# LSWM_10_STM32L0_ADXL345.net
KiCad netlist of a schematic drawn in Altium Designer
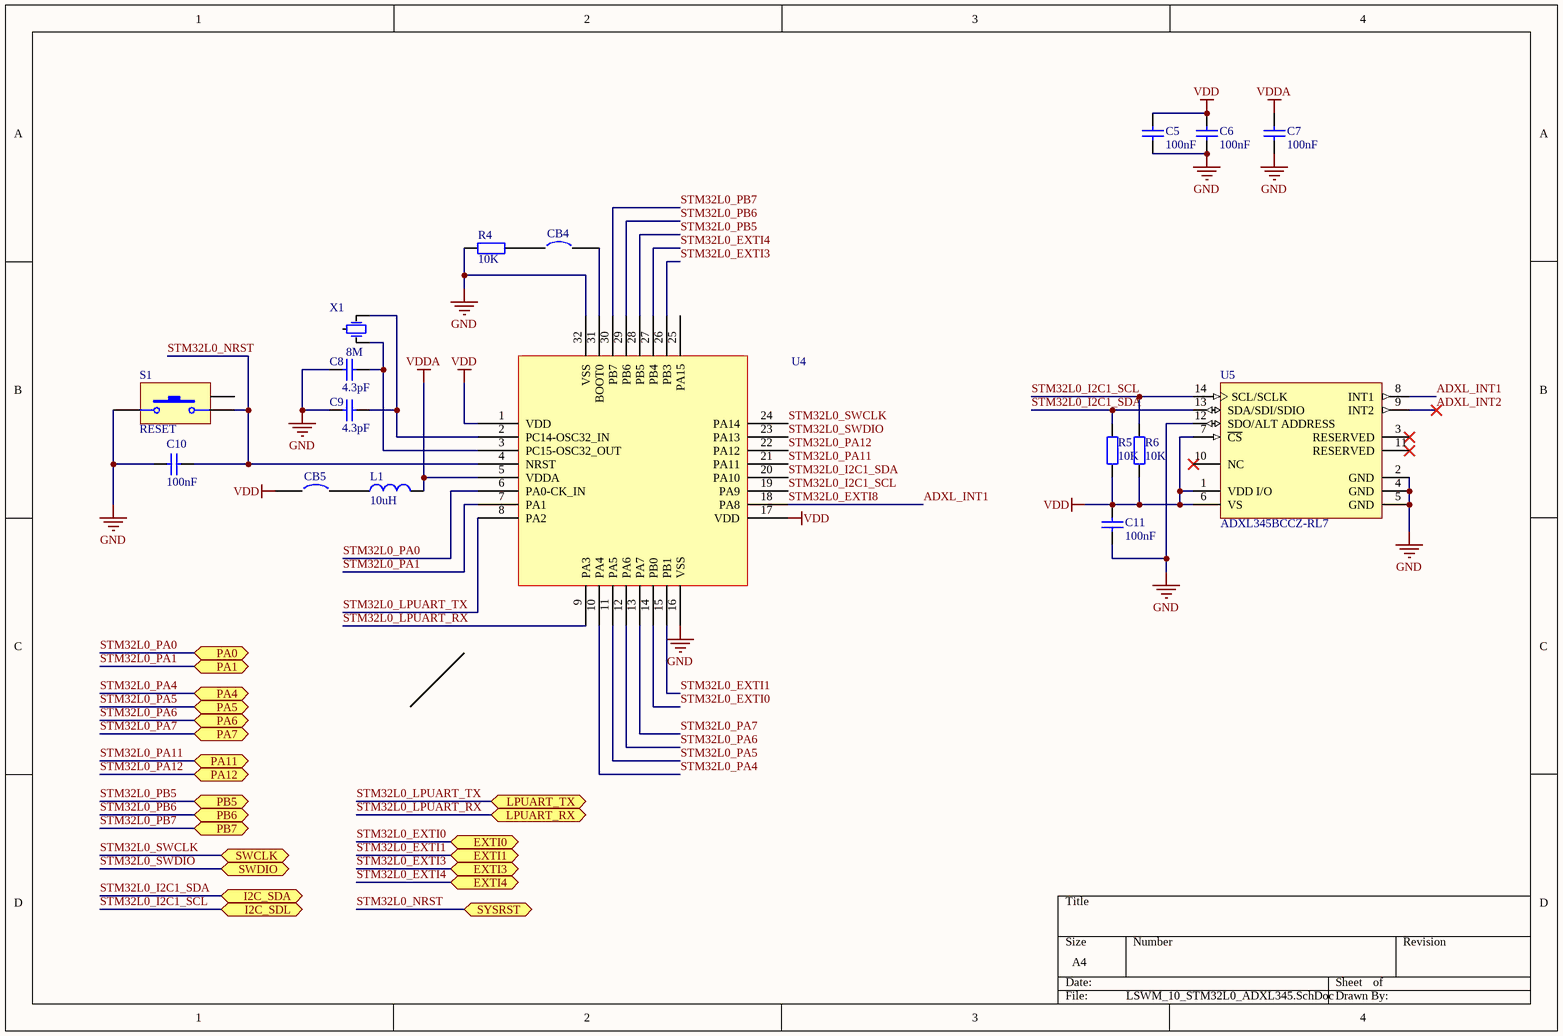
[diagram p0: LSWM_10_STM32L0_ADXL345.SchDoc]

(export (version "E")
  (design (tool "Eeschema 10.0.6"))
  (components
    (comp (ref "C5")
      (value "100nF")
      (footprint "C-RAD-0603")
      (description "无极性电容")
      (fields (field (name "Comment") "Cap") (field (name "PUBLISHER") "Altium Limited"))
      (libsource (lib "fszhang") (part "Cap"))
    )
    (comp (ref "C6")
      (value "100nF")
      (footprint "C-RAD-0603")
      (description "无极性电容")
      (fields (field (name "Comment") "Cap") (field (name "PUBLISHER") "Altium Limited"))
      (libsource (lib "fszhang") (part "Cap"))
    )
    (comp (ref "C7")
      (value "100nF")
      (footprint "C-RAD-0603")
      (description "无极性电容")
      (fields (field (name "Comment") "Cap") (field (name "PUBLISHER") "Altium Limited"))
      (libsource (lib "fszhang") (part "Cap"))
    )
    (comp (ref "C8")
      (value "4.3pF")
      (footprint "C-RAD-0603")
      (description "无极性电容")
      (fields (field (name "Comment") "Cap") (field (name "PUBLISHER") "Altium Limited"))
      (libsource (lib "fszhang") (part "Cap"))
    )
    (comp (ref "C9")
      (value "4.3pF")
      (footprint "C-RAD-0603")
      (description "无极性电容")
      (fields (field (name "Comment") "Cap") (field (name "PUBLISHER") "Altium Limited"))
      (libsource (lib "fszhang") (part "Cap"))
    )
    (comp (ref "C10")
      (value "100nF")
      (footprint "C-RAD-0603")
      (description "无极性电容")
      (fields (field (name "Comment") "Cap") (field (name "PUBLISHER") "Altium Limited"))
      (libsource (lib "fszhang") (part "Cap"))
    )
    (comp (ref "C11")
      (value "100nF")
      (footprint "C-RAD-0603")
      (description "无极性电容")
      (fields (field (name "Comment") "Cap") (field (name "PUBLISHER") "Altium Limited"))
      (libsource (lib "fszhang") (part "Cap"))
    )
    (comp (ref "CB4")
      (value "Circuit Breaker")
      (footprint "SB-0805")
      (fields (field (name "PUBLISHER") "Altium Limited"))
      (libsource (lib "Schlib1") (part "Circuit Breaker"))
    )
    (comp (ref "CB5")
      (value "Circuit Breaker")
      (footprint "SB-0805")
      (fields (field (name "PUBLISHER") "Altium Limited"))
      (libsource (lib "Schlib1") (part "Circuit Breaker"))
    )
    (comp (ref "L1")
      (value "10uH")
      (footprint "0805-1")
      (description "电感")
      (fields (field (name "Comment") "Inductor") (field (name "PUBLISHER") "Altium Limited"))
      (libsource (lib "fszhang") (part "Inductor"))
    )
    (comp (ref "R4")
      (value "10K")
      (footprint "0603-1")
      (description "贴片电阻")
      (fields (field (name "Comment") "Res1") (field (name "PUBLISHER") "Altium Limited"))
      (libsource (lib "") (part "Res1_1"))
    )
    (comp (ref "R5")
      (value "10K")
      (footprint "0603-1")
      (description "贴片电阻")
      (fields (field (name "Comment") "Res1") (field (name "PUBLISHER") "Altium Limited"))
      (libsource (lib "fszhang") (part "Res1"))
    )
    (comp (ref "R6")
      (value "10K")
      (footprint "0603-1")
      (description "贴片电阻")
      (fields (field (name "Comment") "Res1") (field (name "PUBLISHER") "Altium Limited"))
      (libsource (lib "fszhang") (part "Res1"))
    )
    (comp (ref "S1")
      (value "RESET")
      (footprint "BTN_2_4_35")
      (description "微动开关")
      (fields (field (name "PUBLISHER") "Altium Limited"))
      (libsource (lib "Schlib1") (part "SW-PB"))
    )
    (comp (ref "U4")
      (value "STM32L031K6")
      (footprint "TQFP80P900X900X160-32N")
      (libsource (lib "Schlib1") (part "STM32L031K6"))
    )
    (comp (ref "U5")
      (value "ADXL345BCCZ-RL7")
      (footprint "LGA80P300X500-14N")
      (libsource (lib "Schlib1") (part "ADI-ADXL34X-CC-14-1"))
    )
    (comp (ref "X1")
      (value "8M")
      (footprint "X-2X6C - duplicate")
      (description "圆柱晶振")
      (fields (field (name "Comment") "XTAL_SM") (field (name "PUBLISHER") "Altium Limited"))
      (libsource (lib "fszhang") (part "XTAL_SM"))
    )
  )
  (nets
    (net (code "1") (name "/ADXL_INT1") (class "Default")
      (node (ref "U4") (pin "18") (pinfunction "PA8_18") (pintype "passive"))
      (node (ref "U5") (pin "8") (pinfunction "INT1_8") (pintype "output"))
    )
    (net (code "2") (name "/ADXL_INT2") (class "Default")
      (node (ref "U5") (pin "9") (pinfunction "INT2_9") (pintype "output+no_connect"))
    )
    (net (code "3") (name "/STM32L0_EXTI0") (class "Default")
      (node (ref "U4") (pin "14") (pinfunction "PB0_14") (pintype "passive"))
    )
    (net (code "4") (name "/STM32L0_EXTI1") (class "Default")
      (node (ref "U4") (pin "15") (pinfunction "PB1_15") (pintype "passive"))
    )
    (net (code "5") (name "/STM32L0_EXTI3") (class "Default")
      (node (ref "U4") (pin "26") (pinfunction "PB3_26") (pintype "passive"))
    )
    (net (code "6") (name "/STM32L0_EXTI4") (class "Default")
      (node (ref "U4") (pin "27") (pinfunction "PB4_27") (pintype "passive"))
    )
    (net (code "7") (name "/STM32L0_I2C1_SCL") (class "Default")
      (node (ref "R6") (pin "2") (pinfunction "2_2") (pintype "passive"))
      (node (ref "U4") (pin "19") (pinfunction "PA9_19") (pintype "passive"))
      (node (ref "U5") (pin "14") (pinfunction "SCL/SCLK_14") (pintype "input"))
    )
    (net (code "8") (name "/STM32L0_I2C1_SDA") (class "Default")
      (node (ref "R5") (pin "2") (pinfunction "2_2") (pintype "passive"))
      (node (ref "U4") (pin "20") (pinfunction "PA10_20") (pintype "passive"))
      (node (ref "U5") (pin "13") (pinfunction "SDA/SDI/SDIO_13") (pintype "bidirectional"))
    )
    (net (code "9") (name "/STM32L0_LPUART_RX") (class "Default")
      (node (ref "U4") (pin "9") (pinfunction "PA3_9") (pintype "passive"))
    )
    (net (code "10") (name "/STM32L0_LPUART_TX") (class "Default")
      (node (ref "U4") (pin "8") (pinfunction "PA2_8") (pintype "passive"))
    )
    (net (code "11") (name "/STM32L0_NRST") (class "Default")
      (node (ref "C10") (pin "2") (pinfunction "2_2") (pintype "passive"))
      (node (ref "S1") (pin "2") (pinfunction "2_2") (pintype "passive"))
      (node (ref "U4") (pin "4") (pinfunction "NRST_4") (pintype "passive"))
    )
    (net (code "12") (name "/STM32L0_PA0") (class "Default")
      (node (ref "U4") (pin "6") (pinfunction "PA0-CK_IN_6") (pintype "passive"))
    )
    (net (code "13") (name "/STM32L0_PA1") (class "Default")
      (node (ref "U4") (pin "7") (pinfunction "PA1_7") (pintype "passive"))
    )
    (net (code "14") (name "/STM32L0_PA4") (class "Default")
      (node (ref "U4") (pin "10") (pinfunction "PA4_10") (pintype "passive"))
    )
    (net (code "15") (name "/STM32L0_PA5") (class "Default")
      (node (ref "U4") (pin "11") (pinfunction "PA5_11") (pintype "passive"))
    )
    (net (code "16") (name "/STM32L0_PA6") (class "Default")
      (node (ref "U4") (pin "12") (pinfunction "PA6_12") (pintype "passive"))
    )
    (net (code "17") (name "/STM32L0_PA7") (class "Default")
      (node (ref "U4") (pin "13") (pinfunction "PA7_13") (pintype "passive"))
    )
    (net (code "18") (name "/STM32L0_PA11") (class "Default")
      (node (ref "U4") (pin "21") (pinfunction "PA11_21") (pintype "passive"))
    )
    (net (code "19") (name "/STM32L0_PA12") (class "Default")
      (node (ref "U4") (pin "22") (pinfunction "PA12_22") (pintype "passive"))
    )
    (net (code "20") (name "/STM32L0_PB5") (class "Default")
      (node (ref "U4") (pin "28") (pinfunction "PB5_28") (pintype "passive"))
    )
    (net (code "21") (name "/STM32L0_PB6") (class "Default")
      (node (ref "U4") (pin "29") (pinfunction "PB6_29") (pintype "passive"))
    )
    (net (code "22") (name "/STM32L0_PB7") (class "Default")
      (node (ref "U4") (pin "30") (pinfunction "PB7_30") (pintype "passive"))
    )
    (net (code "23") (name "/STM32L0_SWCLK") (class "Default")
      (node (ref "U4") (pin "24") (pinfunction "PA14_24") (pintype "passive"))
    )
    (net (code "24") (name "/STM32L0_SWDIO") (class "Default")
      (node (ref "U4") (pin "23") (pinfunction "PA13_23") (pintype "passive"))
    )
    (net (code "25") (name "GND") (class "Default")
      (node (ref "C10") (pin "1") (pinfunction "1_1") (pintype "passive"))
      (node (ref "C11") (pin "1") (pinfunction "1_1") (pintype "passive"))
      (node (ref "C5") (pin "2") (pinfunction "2_2") (pintype "passive"))
      (node (ref "C6") (pin "1") (pinfunction "1_1") (pintype "passive"))
      (node (ref "C7") (pin "1") (pinfunction "1_1") (pintype "passive"))
      (node (ref "C8") (pin "1") (pinfunction "1_1") (pintype "passive"))
      (node (ref "C9") (pin "1") (pinfunction "1_1") (pintype "passive"))
      (node (ref "R4") (pin "1") (pinfunction "1_1") (pintype "passive"))
      (node (ref "S1") (pin "1") (pinfunction "1_1") (pintype "passive"))
      (node (ref "U4") (pin "16") (pinfunction "VSS_16") (pintype "passive"))
      (node (ref "U4") (pin "32") (pinfunction "VSS_32") (pintype "passive"))
      (node (ref "U5") (pin "12") (pinfunction "SDO/ALT_ADDRESS_12") (pintype "bidirectional"))
      (node (ref "U5") (pin "2") (pinfunction "GND_2") (pintype "power_in"))
      (node (ref "U5") (pin "4") (pinfunction "GND_4") (pintype "power_in"))
      (node (ref "U5") (pin "5") (pinfunction "GND_5") (pintype "power_in"))
    )
    (net (code "26") (name "Net-(CB4-Pad1)") (class "Default")
      (node (ref "CB4") (pin "1") (pinfunction "1_1") (pintype "passive"))
      (node (ref "R4") (pin "2") (pinfunction "2_2") (pintype "passive"))
    )
    (net (code "27") (name "Net-(CB5-Pad2)") (class "Default")
      (node (ref "CB5") (pin "2") (pinfunction "2_2") (pintype "passive"))
      (node (ref "L1") (pin "1") (pinfunction "1_1") (pintype "passive"))
    )
    (net (code "28") (name "Net-(U4-BOOT0)") (class "Default")
      (node (ref "CB4") (pin "2") (pinfunction "2_2") (pintype "passive"))
      (node (ref "U4") (pin "31") (pinfunction "BOOT0_31") (pintype "passive"))
    )
    (net (code "29") (name "Net-(U4-PC14-OSC32_IN)") (class "Default")
      (node (ref "C9") (pin "2") (pinfunction "2_2") (pintype "passive"))
      (node (ref "U4") (pin "2") (pinfunction "PC14-OSC32_IN_2") (pintype "passive"))
      (node (ref "X1") (pin "1") (pinfunction "OSC1_1") (pintype "passive"))
    )
    (net (code "30") (name "Net-(U4-PC15-OSC32_OUT)") (class "Default")
      (node (ref "C8") (pin "2") (pinfunction "2_2") (pintype "passive"))
      (node (ref "U4") (pin "3") (pinfunction "PC15-OSC32_OUT_3") (pintype "passive"))
      (node (ref "X1") (pin "2") (pinfunction "OSC2_2") (pintype "passive"))
    )
    (net (code "31") (name "VDD") (class "Default")
      (node (ref "C11") (pin "2") (pinfunction "2_2") (pintype "passive"))
      (node (ref "C5") (pin "1") (pinfunction "1_1") (pintype "passive"))
      (node (ref "C6") (pin "2") (pinfunction "2_2") (pintype "passive"))
      (node (ref "CB5") (pin "1") (pinfunction "1_1") (pintype "passive"))
      (node (ref "R5") (pin "1") (pinfunction "1_1") (pintype "passive"))
      (node (ref "R6") (pin "1") (pinfunction "1_1") (pintype "passive"))
      (node (ref "U4") (pin "1") (pinfunction "VDD_1") (pintype "passive"))
      (node (ref "U4") (pin "17") (pinfunction "VDD_17") (pintype "passive"))
      (node (ref "U5") (pin "1") (pinfunction "VDD_I/O_1") (pintype "power_in"))
      (node (ref "U5") (pin "6") (pinfunction "VS_6") (pintype "power_in"))
      (node (ref "U5") (pin "7") (pinfunction "~{CS}_7") (pintype "input"))
    )
    (net (code "32") (name "VDDA") (class "Default")
      (node (ref "C7") (pin "2") (pinfunction "2_2") (pintype "passive"))
      (node (ref "L1") (pin "2") (pinfunction "2_2") (pintype "passive"))
      (node (ref "U4") (pin "5") (pinfunction "VDDA_5") (pintype "passive"))
    )
    (net (code "33") (name "unconnected-(S1-Pad3)") (class "Default")
      (node (ref "S1") (pin "3") (pinfunction "3_3") (pintype "passive"))
    )
    (net (code "34") (name "unconnected-(U4-PA15-Pad25)") (class "Default")
      (node (ref "U4") (pin "25") (pinfunction "PA15_25") (pintype "passive"))
    )
    (net (code "35") (name "unconnected-(U5-NC-Pad10)") (class "Default")
      (node (ref "U5") (pin "10") (pinfunction "NC_10") (pintype "passive+no_connect"))
    )
    (net (code "36") (name "unconnected-(U5-RESERVED-Pad3)") (class "Default")
      (node (ref "U5") (pin "3") (pinfunction "RESERVED_3") (pintype "passive+no_connect"))
    )
    (net (code "37") (name "unconnected-(U5-RESERVED-Pad11)") (class "Default")
      (node (ref "U5") (pin "11") (pinfunction "RESERVED_11") (pintype "passive+no_connect"))
    )
    (net (code "38") (name "unconnected-(X1-Pad3)") (class "Default")
      (node (ref "X1") (pin "3") (pinfunction "3_3") (pintype "passive"))
    )
  )
)
